# UART_JTAG.net
KiCad netlist of a schematic drawn in Altium Designer
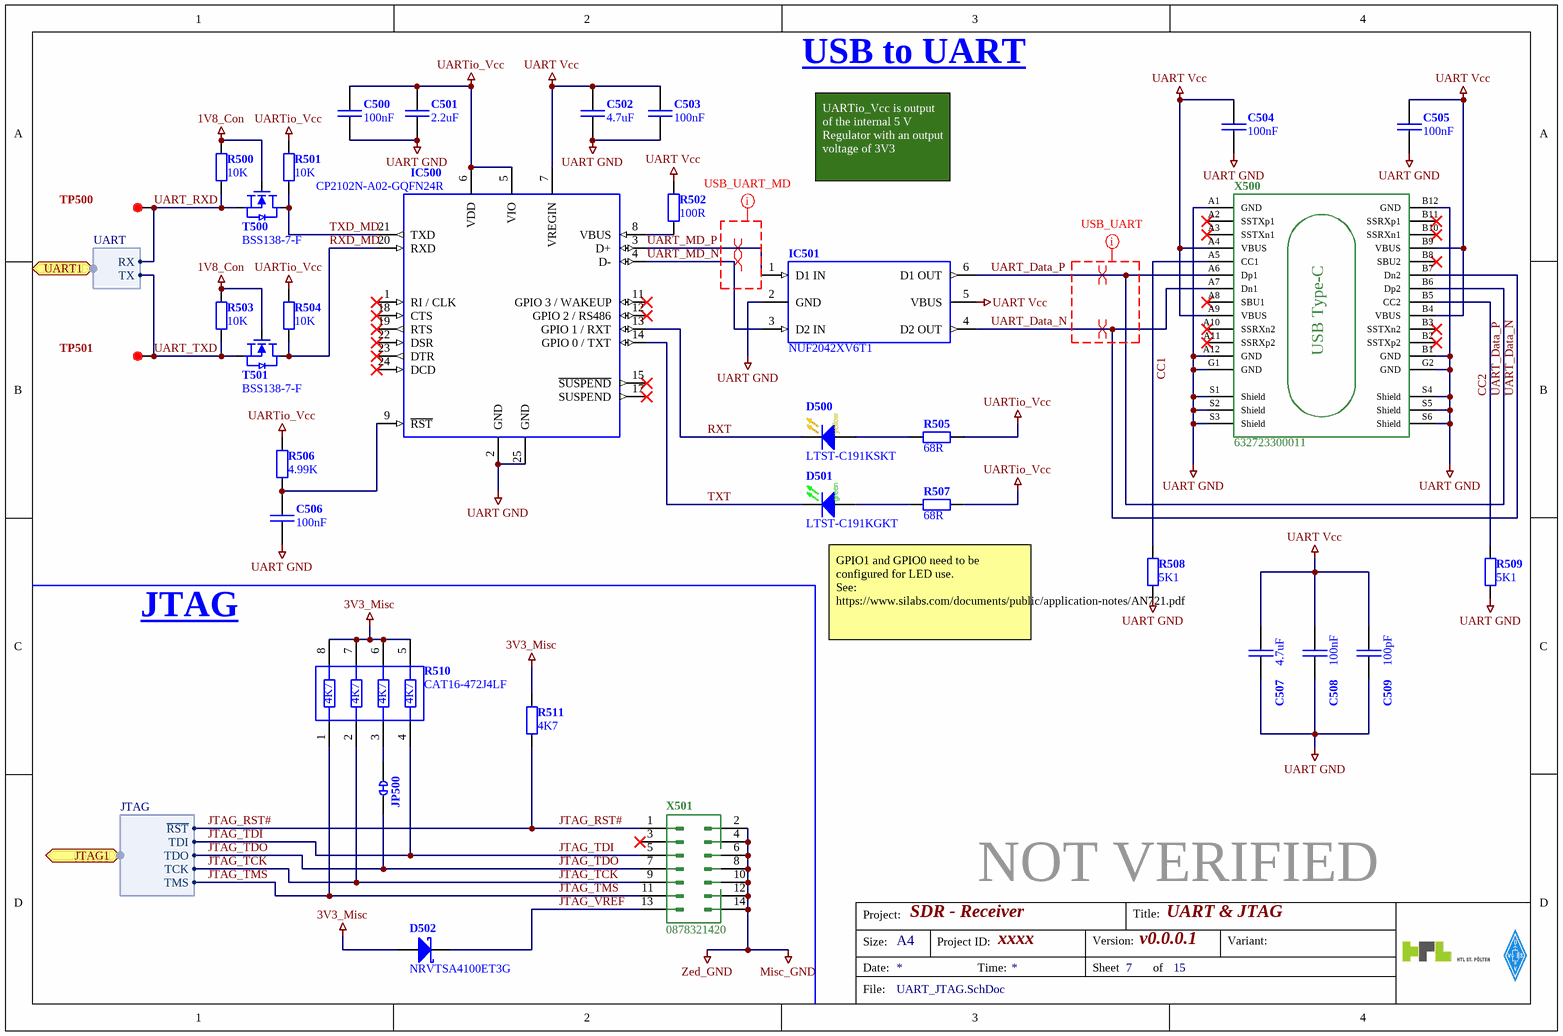
[diagram p0: UART_JTAG.SchDoc]

(export (version "E")
  (design (tool "Eeschema 10.0.6"))
  (components
    (comp (ref "C500")
      (value "100nF")
      (footprint "PrometheusLib:C_0603_N [CAPC1608N IPC]")
      (libsource (lib "PrometheusLib") (part "C_GENERIC"))
    )
    (comp (ref "C501")
      (value "2.2uF")
      (footprint "PrometheusLib:C_0805_N [CAPC2013N IPC]")
      (libsource (lib "PrometheusLib") (part "C_GENERIC"))
    )
    (comp (ref "C502")
      (value "4.7uF")
      (footprint "PrometheusLib:C_0805_N [CAPC2013N IPC]")
      (libsource (lib "PrometheusLib") (part "C_GENERIC"))
    )
    (comp (ref "C503")
      (value "100nF")
      (footprint "PrometheusLib:C_0603_N [CAPC1608N IPC]")
      (libsource (lib "PrometheusLib") (part "C_GENERIC"))
    )
    (comp (ref "C504")
      (value "100nF")
      (footprint "PrometheusLib:C_0603_N [CAPC1608N IPC]")
      (libsource (lib "PrometheusLib") (part "C_GENERIC"))
    )
    (comp (ref "C505")
      (value "100nF")
      (footprint "PrometheusLib:C_0603_N [CAPC1608N IPC]")
      (libsource (lib "PrometheusLib") (part "C_GENERIC"))
    )
    (comp (ref "C506")
      (value "100nF")
      (footprint "PrometheusLib:C_0603_N [CAPC1608N IPC]")
      (libsource (lib "PrometheusLib") (part "C_GENERIC"))
    )
    (comp (ref "C507")
      (value "4.7uF")
      (footprint "PrometheusLib:C_1210_N [CAPC3225N IPC]")
      (libsource (lib "PrometheusLib") (part "C_GENERIC"))
    )
    (comp (ref "C508")
      (value "100nF")
      (footprint "PrometheusLib:C_0805_N [CAPC2013N IPC]")
      (libsource (lib "PrometheusLib") (part "C_GENERIC"))
    )
    (comp (ref "C509")
      (value "100pF")
      (footprint "PrometheusLib:C_0603_N [CAPC1608N IPC]")
      (libsource (lib "PrometheusLib") (part "C_GENERIC"))
    )
    (comp (ref "D500")
      (value "LTST-C191KSKT")
      (footprint "LED_0603-YELLOW_N_AK")
      (libsource (lib "PrometheusLib") (part "LED_YELLOW_GENERIC"))
    )
    (comp (ref "D501")
      (value "LTST-C191KGKT")
      (footprint "PrometheusLib:LED_0603-GREEN_N_AK")
      (libsource (lib "PrometheusLib") (part "LED_GREEN_GENERIC"))
    )
    (comp (ref "D502")
      (value "NRVTSA4100ET3G")
      (footprint "DIOM4326X22N IPC")
      (description "max. Vr = 100 V\r\nmax Vf = 680 mV")
      (libsource (lib "PrometheusLib") (part "D_SCHOTTKY_NRVTSA4100E"))
    )
    (comp (ref "IC500")
      (value "CP2102N-A02-GQFN24R")
      (footprint "QFN50P400X400X80_HS-25N IPC")
      (libsource (lib "PrometheusLib") (part "IC_CP2102N"))
    )
    (comp (ref "IC501")
      (value "NUF2042XV6T1")
      (footprint "SOTFL50P160X60-6N IPC")
      (libsource (lib "PrometheusLib") (part "IC_NUF2042XV6T1"))
    )
    (comp (ref "JP500")
      (value "JP_Connected")
      (footprint "JP_Connected")
      (libsource (lib "PrometheusLib") (part "JP_Connected"))
    )
    (comp (ref "R500")
      (value "10K")
      (footprint "PrometheusLib:R_0201_L [RESC0603L IPC]")
      (libsource (lib "") (part "R_GENERIC_DIN_1"))
    )
    (comp (ref "R501")
      (value "10K")
      (footprint "PrometheusLib:R_0201_L [RESC0603L IPC]")
      (libsource (lib "") (part "R_GENERIC_DIN_1"))
    )
    (comp (ref "R502")
      (value "100R")
      (footprint "PrometheusLib:R_0603_N [RESC1608N IPC]")
      (libsource (lib "") (part "R_GENERIC_DIN_2"))
    )
    (comp (ref "R503")
      (value "10K")
      (footprint "PrometheusLib:R_0201_L [RESC0603L IPC]")
      (libsource (lib "") (part "R_GENERIC_DIN_1"))
    )
    (comp (ref "R504")
      (value "10K")
      (footprint "PrometheusLib:R_0201_L [RESC0603L IPC]")
      (libsource (lib "") (part "R_GENERIC_DIN_1"))
    )
    (comp (ref "R505")
      (value "68R")
      (footprint "PrometheusLib:R_0603_N [RESC1608N IPC]")
      (libsource (lib "PrometheusLib") (part "R_GENERIC_DIN"))
    )
    (comp (ref "R506")
      (value "4.99K")
      (footprint "PrometheusLib:R_0201_L [RESC0603L IPC]")
      (libsource (lib "") (part "R_GENERIC_DIN_1"))
    )
    (comp (ref "R507")
      (value "68R")
      (footprint "PrometheusLib:R_0603_N [RESC1608N IPC]")
      (libsource (lib "PrometheusLib") (part "R_GENERIC_DIN"))
    )
    (comp (ref "R508")
      (value "5K1")
      (footprint "PrometheusLib:R_0603_N [RESC1608N IPC]")
      (libsource (lib "") (part "R_GENERIC_DIN_1"))
    )
    (comp (ref "R509")
      (value "5K1")
      (footprint "PrometheusLib:R_0603_N [RESC1608N IPC]")
      (libsource (lib "") (part "R_GENERIC_DIN_1"))
    )
    (comp (ref "R510")
      (value "CAT16-472J4LF")
      (footprint "CAC-80P320X155-8N")
      (description "Resitor array 4 x 4K7 1206")
      (libsource (lib "PrometheusLib") (part "R_CAT16-472J4LF"))
    )
    (comp (ref "R511")
      (value "4K7")
      (footprint "PrometheusLib:R_0603_N [RESC1608N IPC]")
      (libsource (lib "") (part "R_GENERIC_DIN_1"))
    )
    (comp (ref "T500")
      (value "BSS138-7-F")
      (footprint "SOT105P235X102-3N IPC")
      (libsource (lib "PrometheusLib") (part "T_NMOS_BSS138-7-F"))
    )
    (comp (ref "T501")
      (value "BSS138-7-F")
      (footprint "SOT105P235X102-3N IPC")
      (libsource (lib "PrometheusLib") (part "T_NMOS_BSS138-7-F"))
    )
    (comp (ref "TP500")
      (value "TP_GENERIC")
      (footprint "PrometheusLib:TP_0.8_P100T")
      (description "Needle Test Point")
      (libsource (lib "PrometheusLib") (part "TP_GENERIC"))
    )
    (comp (ref "TP501")
      (value "TP_GENERIC")
      (footprint "PrometheusLib:TP_0.8_P100T")
      (description "Needle Test Point")
      (libsource (lib "PrometheusLib") (part "TP_GENERIC"))
    )
    (comp (ref "X500")
      (value "632723300011")
      (footprint "X_632723300011")
      (description "USB Type-C Receptabel\r\nHorizontal\r\n1.6 mm PCB thickness")
      (libsource (lib "PrometheusLib") (part "X_632723300011"))
    )
    (comp (ref "X501")
      (value "0878321420")
      (footprint "X_SMD_HEADER2x7_P254_H0_Prometheus")
      (description "Pin-Header RM2.54, straight, 7pin, dual row")
      (libsource (lib "PrometheusLib") (part "X_HEADER_SMD_7x2_RM2.54"))
    )
  )
  (nets
    (net (code "3") (name "/CC1") (class "Default")
      (node (ref "R508") (pin "2") (pinfunction "2_2") (pintype "passive"))
      (node (ref "X500") (pin "A5") (pinfunction "CC1_A5") (pintype "passive"))
    )
    (net (code "4") (name "/CC2") (class "Default")
      (node (ref "R509") (pin "2") (pinfunction "2_2") (pintype "passive"))
      (node (ref "X500") (pin "B5") (pinfunction "CC2_B5") (pintype "passive"))
    )
    (net (code "5") (name "/JTAG_RST#") (class "Default")
      (node (ref "R511") (pin "1") (pinfunction "1_1") (pintype "passive"))
      (node (ref "X501") (pin "1") (pinfunction "1_1") (pintype "passive"))
    )
    (net (code "6") (name "/JTAG_TCK") (class "Default")
      (node (ref "R510") (pin "2") (pinfunction "2_2") (pintype "passive"))
      (node (ref "X501") (pin "9") (pinfunction "9_9") (pintype "passive"))
    )
    (net (code "7") (name "/JTAG_TDI") (class "Default")
      (node (ref "R510") (pin "4") (pinfunction "4_4") (pintype "passive"))
      (node (ref "X501") (pin "5") (pinfunction "5_5") (pintype "passive"))
    )
    (net (code "8") (name "/JTAG_TDO") (class "Default")
      (node (ref "JP500") (pin "2") (pinfunction "-_2") (pintype "passive"))
      (node (ref "X501") (pin "7") (pinfunction "7_7") (pintype "passive"))
    )
    (net (code "9") (name "/JTAG_TMS") (class "Default")
      (node (ref "R510") (pin "1") (pinfunction "1_1") (pintype "passive"))
      (node (ref "X501") (pin "11") (pinfunction "11_11") (pintype "passive"))
    )
    (net (code "10") (name "/JTAG_VREF") (class "Default")
      (node (ref "D502") (pin "K") (pinfunction "K_K") (pintype "passive"))
      (node (ref "X501") (pin "13") (pinfunction "13_13") (pintype "passive"))
    )
    (net (code "11") (name "/RXD_MD") (class "Default")
      (node (ref "IC500") (pin "20") (pinfunction "RXD_20") (pintype "input"))
      (node (ref "R504") (pin "1") (pinfunction "1_1") (pintype "passive"))
      (node (ref "T501") (pin "D") (pinfunction "D_D") (pintype "passive"))
    )
    (net (code "12") (name "/RXT") (class "Default")
      (node (ref "D500") (pin "K") (pinfunction "K_K") (pintype "passive"))
      (node (ref "IC500") (pin "13") (pinfunction "GPIO_1_/_RXT_13") (pintype "bidirectional"))
    )
    (net (code "13") (name "/TXD_MD") (class "Default")
      (node (ref "IC500") (pin "21") (pinfunction "TXD_21") (pintype "output"))
      (node (ref "R501") (pin "1") (pinfunction "1_1") (pintype "passive"))
      (node (ref "T500") (pin "D") (pinfunction "D_D") (pintype "passive"))
    )
    (net (code "14") (name "/TXT") (class "Default")
      (node (ref "D501") (pin "K") (pinfunction "K_K") (pintype "passive"))
      (node (ref "IC500") (pin "14") (pinfunction "GPIO_0_/_TXT_14") (pintype "bidirectional"))
    )
    (net (code "15") (name "/UART_Data_N") (class "Default")
      (node (ref "IC501") (pin "4") (pinfunction "D2_OUT_4") (pintype "output"))
      (node (ref "X500") (pin "A7") (pinfunction "Dn1_A7") (pintype "passive"))
      (node (ref "X500") (pin "B7") (pinfunction "Dn2_B7") (pintype "passive"))
    )
    (net (code "16") (name "/UART_Data_P") (class "Default")
      (node (ref "IC501") (pin "6") (pinfunction "D1_OUT_6") (pintype "output"))
      (node (ref "X500") (pin "A6") (pinfunction "Dp1_A6") (pintype "passive"))
      (node (ref "X500") (pin "B6") (pinfunction "Dp2_B6") (pintype "passive"))
    )
    (net (code "17") (name "/UART_MD_N") (class "Default")
      (node (ref "IC500") (pin "4") (pinfunction "D-_4") (pintype "bidirectional"))
      (node (ref "IC501") (pin "3") (pinfunction "D2_IN_3") (pintype "input"))
    )
    (net (code "18") (name "/UART_MD_P") (class "Default")
      (node (ref "IC500") (pin "3") (pinfunction "D+_3") (pintype "bidirectional"))
      (node (ref "IC501") (pin "1") (pinfunction "D1_IN_1") (pintype "input"))
    )
    (net (code "19") (name "/UART_RXD") (class "Default")
      (node (ref "R500") (pin "1") (pinfunction "1_1") (pintype "passive"))
      (node (ref "T500") (pin "S") (pinfunction "S_S") (pintype "passive"))
      (node (ref "TP500") (pin "1") (pinfunction "1_1") (pintype "passive"))
    )
    (net (code "20") (name "/UART_TXD") (class "Default")
      (node (ref "R503") (pin "1") (pinfunction "1_1") (pintype "passive"))
      (node (ref "T501") (pin "S") (pinfunction "S_S") (pintype "passive"))
      (node (ref "TP501") (pin "1") (pinfunction "1_1") (pintype "passive"))
    )
    (net (code "23") (name "1V8_Con") (class "Default")
      (node (ref "R500") (pin "2") (pinfunction "2_2") (pintype "passive"))
      (node (ref "R503") (pin "2") (pinfunction "2_2") (pintype "passive"))
      (node (ref "T500") (pin "G") (pinfunction "G_G") (pintype "passive"))
      (node (ref "T501") (pin "G") (pinfunction "G_G") (pintype "passive"))
    )
    (net (code "24") (name "3V3_Misc") (class "Default")
      (node (ref "D502") (pin "A") (pinfunction "A_A") (pintype "passive"))
      (node (ref "R510") (pin "5") (pinfunction "5_5") (pintype "passive"))
      (node (ref "R510") (pin "6") (pinfunction "6_6") (pintype "passive"))
      (node (ref "R510") (pin "7") (pinfunction "7_7") (pintype "passive"))
      (node (ref "R510") (pin "8") (pinfunction "8_8") (pintype "passive"))
      (node (ref "R511") (pin "2") (pinfunction "2_2") (pintype "passive"))
    )
    (net (code "25") (name "Misc_GND") (class "Default")
      (node (ref "X501") (pin "10") (pinfunction "10_10") (pintype "passive"))
      (node (ref "X501") (pin "12") (pinfunction "12_12") (pintype "passive"))
      (node (ref "X501") (pin "14") (pinfunction "14_14") (pintype "passive"))
      (node (ref "X501") (pin "2") (pinfunction "2_2") (pintype "passive"))
      (node (ref "X501") (pin "4") (pinfunction "4_4") (pintype "passive"))
      (node (ref "X501") (pin "6") (pinfunction "6_6") (pintype "passive"))
      (node (ref "X501") (pin "8") (pinfunction "8_8") (pintype "passive"))
    )
    (net (code "26") (name "Net-(D500-PadA)") (class "Default")
      (node (ref "D500") (pin "A") (pinfunction "A_A") (pintype "passive"))
      (node (ref "R505") (pin "2") (pinfunction "2_2") (pintype "passive"))
    )
    (net (code "27") (name "Net-(D501-PadA)") (class "Default")
      (node (ref "D501") (pin "A") (pinfunction "A_A") (pintype "passive"))
      (node (ref "R507") (pin "2") (pinfunction "2_2") (pintype "passive"))
    )
    (net (code "28") (name "Net-(IC500-VBUS)") (class "Default")
      (node (ref "IC500") (pin "8") (pinfunction "VBUS_8") (pintype "input"))
      (node (ref "R502") (pin "2") (pinfunction "2_2") (pintype "passive"))
    )
    (net (code "29") (name "Net-(IC500-~{RST})") (class "Default")
      (node (ref "C506") (pin "1") (pintype "passive"))
      (node (ref "IC500") (pin "9") (pinfunction "~{RST}_9") (pintype "input"))
      (node (ref "R506") (pin "1") (pinfunction "1_1") (pintype "passive"))
    )
    (net (code "30") (name "Net-(JP500-+)") (class "Default")
      (node (ref "JP500") (pin "1") (pinfunction "+_1") (pintype "passive"))
      (node (ref "R510") (pin "3") (pinfunction "3_3") (pintype "passive"))
    )
    (net (code "31") (name "UART GND") (class "Default")
      (node (ref "C500") (pin "2") (pintype "passive"))
      (node (ref "C501") (pin "2") (pintype "passive"))
      (node (ref "C502") (pin "2") (pintype "passive"))
      (node (ref "C503") (pin "2") (pintype "passive"))
      (node (ref "C504") (pin "2") (pintype "passive"))
      (node (ref "C505") (pin "2") (pintype "passive"))
      (node (ref "C506") (pin "2") (pintype "passive"))
      (node (ref "C507") (pin "2") (pintype "passive"))
      (node (ref "C508") (pin "2") (pintype "passive"))
      (node (ref "C509") (pin "2") (pintype "passive"))
      (node (ref "IC500") (pin "2") (pinfunction "GND_2") (pintype "passive"))
      (node (ref "IC500") (pin "25") (pinfunction "GND_25") (pintype "passive"))
      (node (ref "IC501") (pin "2") (pinfunction "GND_2") (pintype "passive"))
      (node (ref "R508") (pin "1") (pinfunction "1_1") (pintype "passive"))
      (node (ref "R509") (pin "1") (pinfunction "1_1") (pintype "passive"))
      (node (ref "X500") (pin "A1") (pinfunction "GND_A1") (pintype "passive"))
      (node (ref "X500") (pin "A12") (pinfunction "GND_A12") (pintype "passive"))
      (node (ref "X500") (pin "B1") (pinfunction "GND_B1") (pintype "passive"))
      (node (ref "X500") (pin "B12") (pinfunction "GND_B12") (pintype "passive"))
      (node (ref "X500") (pin "G1") (pinfunction "GND_G1") (pintype "passive"))
      (node (ref "X500") (pin "G2") (pinfunction "GND_G2") (pintype "passive"))
      (node (ref "X500") (pin "S1") (pinfunction "Shield_S1") (pintype "passive"))
      (node (ref "X500") (pin "S2") (pinfunction "Shield_S2") (pintype "passive"))
      (node (ref "X500") (pin "S3") (pinfunction "Shield_S3") (pintype "passive"))
      (node (ref "X500") (pin "S4") (pinfunction "Shield_S4") (pintype "passive"))
      (node (ref "X500") (pin "S5") (pinfunction "Shield_S5") (pintype "passive"))
      (node (ref "X500") (pin "S6") (pinfunction "Shield_S6") (pintype "passive"))
    )
    (net (code "32") (name "UART Vcc") (class "Default")
      (node (ref "C502") (pin "1") (pintype "passive"))
      (node (ref "C503") (pin "1") (pintype "passive"))
      (node (ref "C504") (pin "1") (pintype "passive"))
      (node (ref "C505") (pin "1") (pintype "passive"))
      (node (ref "C507") (pin "1") (pintype "passive"))
      (node (ref "C508") (pin "1") (pintype "passive"))
      (node (ref "C509") (pin "1") (pintype "passive"))
      (node (ref "IC500") (pin "7") (pinfunction "VREGIN_7") (pintype "passive"))
      (node (ref "IC501") (pin "5") (pinfunction "VBUS_5") (pintype "passive"))
      (node (ref "R502") (pin "1") (pinfunction "1_1") (pintype "passive"))
      (node (ref "X500") (pin "A4") (pinfunction "VBUS_A4") (pintype "passive"))
      (node (ref "X500") (pin "A9") (pinfunction "VBUS_A9") (pintype "passive"))
      (node (ref "X500") (pin "B4") (pinfunction "VBUS_B4") (pintype "passive"))
      (node (ref "X500") (pin "B9") (pinfunction "VBUS_B9") (pintype "passive"))
    )
    (net (code "33") (name "UARTio_Vcc") (class "Default")
      (node (ref "C500") (pin "1") (pintype "passive"))
      (node (ref "C501") (pin "1") (pintype "passive"))
      (node (ref "IC500") (pin "5") (pinfunction "VIO_5") (pintype "passive"))
      (node (ref "IC500") (pin "6") (pinfunction "VDD_6") (pintype "passive"))
      (node (ref "R501") (pin "2") (pinfunction "2_2") (pintype "passive"))
      (node (ref "R504") (pin "2") (pinfunction "2_2") (pintype "passive"))
      (node (ref "R505") (pin "1") (pinfunction "1_1") (pintype "passive"))
      (node (ref "R506") (pin "2") (pinfunction "2_2") (pintype "passive"))
      (node (ref "R507") (pin "1") (pinfunction "1_1") (pintype "passive"))
    )
    (net (code "34") (name "unconnected-(IC500-CTS-Pad18)") (class "Default")
      (node (ref "IC500") (pin "18") (pinfunction "CTS_18") (pintype "input+no_connect"))
    )
    (net (code "35") (name "unconnected-(IC500-DCD-Pad24)") (class "Default")
      (node (ref "IC500") (pin "24") (pinfunction "DCD_24") (pintype "input+no_connect"))
    )
    (net (code "36") (name "unconnected-(IC500-DSR-Pad22)") (class "Default")
      (node (ref "IC500") (pin "22") (pinfunction "DSR_22") (pintype "input+no_connect"))
    )
    (net (code "37") (name "unconnected-(IC500-DTR-Pad23)") (class "Default")
      (node (ref "IC500") (pin "23") (pinfunction "DTR_23") (pintype "output+no_connect"))
    )
    (net (code "38") (name "unconnected-(IC500-GPIO_2_{slash}_RS486-Pad12)") (class "Default")
      (node (ref "IC500") (pin "12") (pinfunction "GPIO_2_/_RS486_12") (pintype "bidirectional+no_connect"))
    )
    (net (code "39") (name "unconnected-(IC500-GPIO_3_{slash}_WAKEUP-Pad11)") (class "Default")
      (node (ref "IC500") (pin "11") (pinfunction "GPIO_3_/_WAKEUP_11") (pintype "bidirectional+no_connect"))
    )
    (net (code "40") (name "unconnected-(IC500-RI_{slash}_CLK-Pad1)") (class "Default")
      (node (ref "IC500") (pin "1") (pinfunction "RI_/_CLK_1") (pintype "input+no_connect"))
    )
    (net (code "41") (name "unconnected-(IC500-RTS-Pad19)") (class "Default")
      (node (ref "IC500") (pin "19") (pinfunction "RTS_19") (pintype "output+no_connect"))
    )
    (net (code "42") (name "unconnected-(IC500-SUSPEND-Pad17)") (class "Default")
      (node (ref "IC500") (pin "17") (pinfunction "SUSPEND_17") (pintype "output+no_connect"))
    )
    (net (code "43") (name "unconnected-(IC500-~{SUSPEND}-Pad15)") (class "Default")
      (node (ref "IC500") (pin "15") (pinfunction "~{SUSPEND}_15") (pintype "output+no_connect"))
    )
    (net (code "44") (name "unconnected-(X500-SBU1-PadA8)") (class "Default")
      (node (ref "X500") (pin "A8") (pinfunction "SBU1_A8") (pintype "passive+no_connect"))
    )
    (net (code "45") (name "unconnected-(X500-SBU2-PadB8)") (class "Default")
      (node (ref "X500") (pin "B8") (pinfunction "SBU2_B8") (pintype "passive+no_connect"))
    )
    (net (code "46") (name "unconnected-(X500-SSRXn1-PadB10)") (class "Default")
      (node (ref "X500") (pin "B10") (pinfunction "SSRXn1_B10") (pintype "passive+no_connect"))
    )
    (net (code "47") (name "unconnected-(X500-SSRXn2-PadA10)") (class "Default")
      (node (ref "X500") (pin "A10") (pinfunction "SSRXn2_A10") (pintype "passive+no_connect"))
    )
    (net (code "48") (name "unconnected-(X500-SSRXp1-PadB11)") (class "Default")
      (node (ref "X500") (pin "B11") (pinfunction "SSRXp1_B11") (pintype "passive+no_connect"))
    )
    (net (code "49") (name "unconnected-(X500-SSRXp2-PadA11)") (class "Default")
      (node (ref "X500") (pin "A11") (pinfunction "SSRXp2_A11") (pintype "passive+no_connect"))
    )
    (net (code "50") (name "unconnected-(X500-SSTXn1-PadA3)") (class "Default")
      (node (ref "X500") (pin "A3") (pinfunction "SSTXn1_A3") (pintype "passive+no_connect"))
    )
    (net (code "51") (name "unconnected-(X500-SSTXn2-PadB3)") (class "Default")
      (node (ref "X500") (pin "B3") (pinfunction "SSTXn2_B3") (pintype "passive+no_connect"))
    )
    (net (code "52") (name "unconnected-(X500-SSTXp1-PadA2)") (class "Default")
      (node (ref "X500") (pin "A2") (pinfunction "SSTXp1_A2") (pintype "passive+no_connect"))
    )
    (net (code "53") (name "unconnected-(X500-SSTXp2-PadB2)") (class "Default")
      (node (ref "X500") (pin "B2") (pinfunction "SSTXp2_B2") (pintype "passive+no_connect"))
    )
    (net (code "54") (name "unconnected-(X501-Pad3)") (class "Default")
      (node (ref "X501") (pin "3") (pinfunction "3_3") (pintype "passive+no_connect"))
    )
  )
)
